# gest-mod.net
KiCad netlist of a schematic drawn in EAGLE
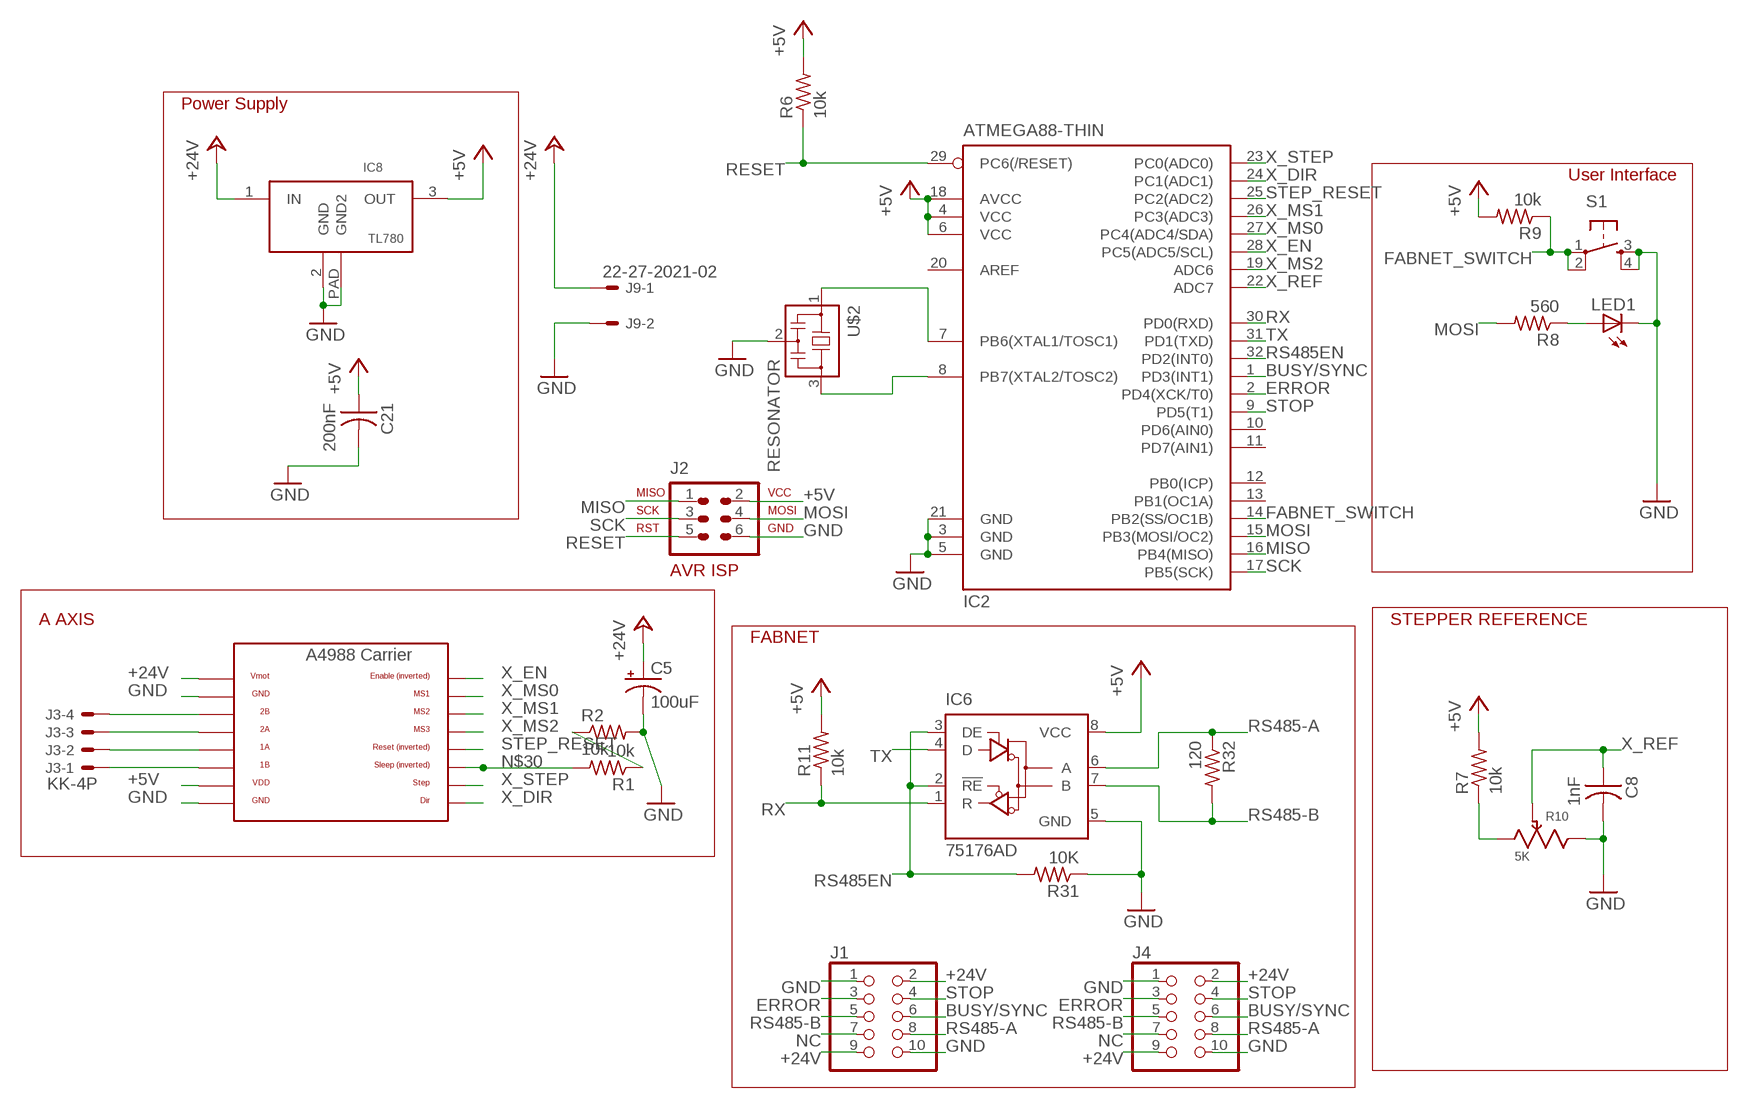
[diagram p0: schematic, sheet 1]

(export (version "E")
  (design (tool "Eeschema 10.0.6"))
  (components
    (comp (ref "C5")
      (value "100uF")
      (footprint "eagle-import:PANASONIC_D")
      (libsource (lib "eagle-import") (part "CPOL-USD"))
    )
    (comp (ref "C8")
      (value "1nF")
      (footprint "eagle-import:C1206FAB")
      (libsource (lib "eagle-import") (part "CAP-US1206FAB"))
    )
    (comp (ref "C21")
      (value "200nF")
      (footprint "eagle-import:C1206FAB")
      (libsource (lib "eagle-import") (part "CAP-US1206FAB"))
    )
    (comp (ref "IC2")
      (value "ATMEGA88-THIN")
      (footprint "eagle-import:TQFP32-08THIN")
      (libsource (lib "eagle-import") (part "ATMEGA88-THIN"))
    )
    (comp (ref "IC6")
      (value "75176AD")
      (footprint "eagle-import:D_R-PDSO-G8")
      (libsource (lib "eagle-import") (part "75176AD"))
    )
    (comp (ref "IC8")
      (value "TL780_VREG")
      (footprint "eagle-import:D2PAK-3")
      (libsource (lib "eagle-import") (part "TL780_VREG"))
    )
    (comp (ref "J1")
      (value "PINHEAD_PINHD-2X5")
      (footprint "eagle-import:PINHEAD_2X05")
      (libsource (lib "eagle-import") (part "PINHEAD_PINHD-2X5"))
    )
    (comp (ref "J2")
      (value "AVR-7_AVR-ISP-6VERT")
      (footprint "eagle-import:AVR-7_AVR-ISP-6")
      (libsource (lib "eagle-import") (part "AVR-7_AVR-ISP-6VERT"))
    )
    (comp (ref "J3")
      (value "KK-4P")
      (footprint "eagle-import:7395-04")
      (libsource (lib "eagle-import") (part "22-?-0405-7048"))
    )
    (comp (ref "J4")
      (value "PINHEAD_PINHD-2X5")
      (footprint "eagle-import:PINHEAD_2X05")
      (libsource (lib "eagle-import") (part "PINHEAD_PINHD-2X5"))
    )
    (comp (ref "J9")
      (value "22-27-2021-02")
      (footprint "eagle-import:6410-02")
      (libsource (lib "eagle-import") (part "22-?-0227-2021"))
    )
    (comp (ref "LED1")
      (value "LEDCHIPLED_1206")
      (footprint "eagle-import:CHIPLED_1206")
      (libsource (lib "eagle-import") (part "LEDCHIPLED_1206"))
    )
    (comp (ref "R1")
      (value "10k")
      (footprint "eagle-import:R1206FAB")
      (libsource (lib "eagle-import") (part "RES-US1206FAB"))
    )
    (comp (ref "R2")
      (value "10k")
      (footprint "eagle-import:R1206FAB")
      (libsource (lib "eagle-import") (part "RES-US1206FAB"))
    )
    (comp (ref "R6")
      (value "10k")
      (footprint "eagle-import:R1206FAB")
      (libsource (lib "eagle-import") (part "RES-US1206FAB"))
    )
    (comp (ref "R7")
      (value "10k")
      (footprint "eagle-import:R1206FAB")
      (libsource (lib "eagle-import") (part "RES-US1206FAB"))
    )
    (comp (ref "R8")
      (value "560")
      (footprint "eagle-import:R1206FAB")
      (libsource (lib "eagle-import") (part "RES-US1206FAB"))
    )
    (comp (ref "R9")
      (value "10k")
      (footprint "eagle-import:R1206FAB")
      (libsource (lib "eagle-import") (part "RES-US1206FAB"))
    )
    (comp (ref "R10")
      (value "5K")
      (footprint "eagle-import:BOURN_TRIM")
      (libsource (lib "eagle-import") (part "BOURN_POT"))
    )
    (comp (ref "R11")
      (value "10k")
      (footprint "eagle-import:R1206FAB")
      (libsource (lib "eagle-import") (part "RES-US1206FAB"))
    )
    (comp (ref "R31")
      (value "10K")
      (footprint "eagle-import:R1206FAB")
      (libsource (lib "eagle-import") (part "RES-US1206FAB"))
    )
    (comp (ref "R32")
      (value "120")
      (footprint "eagle-import:R1206FAB")
      (libsource (lib "eagle-import") (part "RES-US1206FAB"))
    )
    (comp (ref "S1")
      (value "6MM_SWITCH6MM_SWITCH")
      (footprint "eagle-import:6MM_SWITCH")
      (libsource (lib "eagle-import") (part "6MM_SWITCH6MM_SWITCH"))
    )
    (comp (ref "U$2")
      (value "RESONATOR")
      (footprint "eagle-import:EFOBM")
      (libsource (lib "eagle-import") (part "RESONATOR"))
    )
    (comp (ref "U$5")
      (value "REPRAPJR_A4988BREAKOUT")
      (footprint "eagle-import:REPRAPJR_A4988BREAKOUT")
      (libsource (lib "eagle-import") (part "REPRAPJR_A4988BREAKOUT"))
    )
  )
  (nets
    (net (code "1") (name "+5V") (class "Default")
      (node (ref "C21") (pin "1") (pinfunction "1_1") (pintype "passive"))
      (node (ref "IC2") (pin "18") (pinfunction "AVCC_18") (pintype "power_in"))
      (node (ref "IC2") (pin "4") (pinfunction "VCC_4") (pintype "power_in"))
      (node (ref "IC2") (pin "6") (pinfunction "VCC_6") (pintype "power_in"))
      (node (ref "IC6") (pin "8") (pinfunction "VCC_8") (pintype "power_in"))
      (node (ref "IC8") (pin "3") (pinfunction "OUT_3") (pintype "bidirectional"))
      (node (ref "J2") (pin "2") (pinfunction "2_2") (pintype "passive"))
      (node (ref "R11") (pin "2") (pinfunction "2_2") (pintype "passive"))
      (node (ref "R6") (pin "2") (pinfunction "2_2") (pintype "passive"))
      (node (ref "R7") (pin "2") (pinfunction "2_2") (pintype "passive"))
      (node (ref "R9") (pin "2") (pinfunction "2_2") (pintype "passive"))
      (node (ref "U$5") (pin "VDD") (pinfunction "VDD_VDD") (pintype "power_in"))
    )
    (net (code "2") (name "+24V") (class "Default")
      (node (ref "C5") (pin "+") (pinfunction "+_+") (pintype "passive"))
      (node (ref "IC8") (pin "1") (pinfunction "IN_1") (pintype "bidirectional"))
      (node (ref "J1") (pin "2") (pinfunction "2_2") (pintype "passive"))
      (node (ref "J1") (pin "9") (pinfunction "9_9") (pintype "passive"))
      (node (ref "J4") (pin "2") (pinfunction "2_2") (pintype "passive"))
      (node (ref "J4") (pin "9") (pinfunction "9_9") (pintype "passive"))
      (node (ref "J9") (pin "1") (pinfunction "S_1") (pintype "passive"))
      (node (ref "U$5") (pin "VMOT") (pinfunction "VMOT_VMOT") (pintype "power_in"))
    )
    (net (code "3") (name "/BUSY{slash}SYNC") (class "Default")
      (node (ref "IC2") (pin "1") (pinfunction "PD3(INT1)_1") (pintype "bidirectional"))
      (node (ref "J1") (pin "6") (pinfunction "6_6") (pintype "passive"))
      (node (ref "J4") (pin "6") (pinfunction "6_6") (pintype "passive"))
    )
    (net (code "4") (name "/ERROR") (class "Default")
      (node (ref "IC2") (pin "2") (pinfunction "PD4(XCK/T0)_2") (pintype "bidirectional"))
      (node (ref "J1") (pin "3") (pinfunction "3_3") (pintype "passive"))
      (node (ref "J4") (pin "3") (pinfunction "3_3") (pintype "passive"))
    )
    (net (code "5") (name "/FABNET_SWITCH") (class "Default")
      (node (ref "IC2") (pin "14") (pinfunction "PB2(SS/OC1B)_14") (pintype "bidirectional"))
      (node (ref "R9") (pin "1") (pinfunction "1_1") (pintype "passive"))
      (node (ref "S1") (pin "1") (pinfunction "P_1") (pintype "passive"))
      (node (ref "S1") (pin "2") (pinfunction "P1_2") (pintype "passive"))
    )
    (net (code "6") (name "/MISO") (class "Default")
      (node (ref "IC2") (pin "16") (pinfunction "PB4(MISO)_16") (pintype "bidirectional"))
      (node (ref "J2") (pin "1") (pinfunction "1_1") (pintype "passive"))
    )
    (net (code "7") (name "/MOSI") (class "Default")
      (node (ref "IC2") (pin "15") (pinfunction "PB3(MOSI/OC2)_15") (pintype "bidirectional"))
      (node (ref "J2") (pin "4") (pinfunction "4_4") (pintype "passive"))
      (node (ref "R8") (pin "2") (pinfunction "2_2") (pintype "passive"))
    )
    (net (code "8") (name "/N$30") (class "Default")
      (node (ref "R1") (pin "2") (pinfunction "2_2") (pintype "passive"))
      (node (ref "U$5") (pin "SLP") (pinfunction "SLEEP_SLP") (pintype "input"))
    )
    (net (code "9") (name "/NC") (class "Default")
      (node (ref "J1") (pin "7") (pinfunction "7_7") (pintype "passive"))
      (node (ref "J4") (pin "7") (pinfunction "7_7") (pintype "passive"))
    )
    (net (code "10") (name "/RESET") (class "Default")
      (node (ref "IC2") (pin "29") (pinfunction "PC6(/RESET)_29") (pintype "bidirectional"))
      (node (ref "J2") (pin "5") (pinfunction "5_5") (pintype "passive"))
      (node (ref "R6") (pin "1") (pinfunction "1_1") (pintype "passive"))
    )
    (net (code "11") (name "/RS485-A") (class "Default")
      (node (ref "IC6") (pin "6") (pinfunction "A_6") (pintype "output"))
      (node (ref "J1") (pin "8") (pinfunction "8_8") (pintype "passive"))
      (node (ref "J4") (pin "8") (pinfunction "8_8") (pintype "passive"))
      (node (ref "R32") (pin "1") (pinfunction "1_1") (pintype "passive"))
    )
    (net (code "12") (name "/RS485-B") (class "Default")
      (node (ref "IC6") (pin "7") (pinfunction "B_7") (pintype "output"))
      (node (ref "J1") (pin "5") (pinfunction "5_5") (pintype "passive"))
      (node (ref "J4") (pin "5") (pinfunction "5_5") (pintype "passive"))
      (node (ref "R32") (pin "2") (pinfunction "2_2") (pintype "passive"))
    )
    (net (code "13") (name "/RS485EN") (class "Default")
      (node (ref "IC2") (pin "32") (pinfunction "PD2(INT0)_32") (pintype "bidirectional"))
      (node (ref "IC6") (pin "2") (pinfunction "~{RE}_2") (pintype "input"))
      (node (ref "IC6") (pin "3") (pinfunction "DE_3") (pintype "input"))
      (node (ref "R31") (pin "2") (pinfunction "2_2") (pintype "passive"))
    )
    (net (code "14") (name "/RX") (class "Default")
      (node (ref "IC2") (pin "30") (pinfunction "PD0(RXD)_30") (pintype "bidirectional"))
      (node (ref "IC6") (pin "1") (pinfunction "R_1") (pintype "input"))
      (node (ref "R11") (pin "1") (pinfunction "1_1") (pintype "passive"))
    )
    (net (code "15") (name "/SCK") (class "Default")
      (node (ref "IC2") (pin "17") (pinfunction "PB5(SCK)_17") (pintype "bidirectional"))
      (node (ref "J2") (pin "3") (pinfunction "3_3") (pintype "passive"))
    )
    (net (code "16") (name "/STEP_RESET") (class "Default")
      (node (ref "IC2") (pin "25") (pinfunction "PC2(ADC2)_25") (pintype "bidirectional"))
      (node (ref "U$5") (pin "RST") (pinfunction "RST_RST") (pintype "input"))
    )
    (net (code "17") (name "/STOP") (class "Default")
      (node (ref "IC2") (pin "9") (pinfunction "PD5(T1)_9") (pintype "bidirectional"))
      (node (ref "J1") (pin "4") (pinfunction "4_4") (pintype "passive"))
      (node (ref "J4") (pin "4") (pinfunction "4_4") (pintype "passive"))
    )
    (net (code "18") (name "/TX") (class "Default")
      (node (ref "IC2") (pin "31") (pinfunction "PD1(TXD)_31") (pintype "bidirectional"))
      (node (ref "IC6") (pin "4") (pinfunction "D_4") (pintype "input"))
    )
    (net (code "19") (name "/X_DIR") (class "Default")
      (node (ref "IC2") (pin "24") (pinfunction "PC1(ADC1)_24") (pintype "bidirectional"))
      (node (ref "U$5") (pin "DIR") (pinfunction "DIR_DIR") (pintype "input"))
    )
    (net (code "20") (name "/X_EN") (class "Default")
      (node (ref "IC2") (pin "28") (pinfunction "PC5(ADC5/SCL)_28") (pintype "bidirectional"))
      (node (ref "U$5") (pin "EN") (pinfunction "EN_EN") (pintype "input"))
    )
    (net (code "21") (name "/X_MS0") (class "Default")
      (node (ref "IC2") (pin "27") (pinfunction "PC4(ADC4/SDA)_27") (pintype "bidirectional"))
      (node (ref "U$5") (pin "MS1") (pinfunction "MS1_MS1") (pintype "input"))
    )
    (net (code "22") (name "/X_MS1") (class "Default")
      (node (ref "IC2") (pin "26") (pinfunction "PC3(ADC3)_26") (pintype "bidirectional"))
      (node (ref "U$5") (pin "MS2") (pinfunction "MS2_MS2") (pintype "input"))
    )
    (net (code "23") (name "/X_MS2") (class "Default")
      (node (ref "IC2") (pin "19") (pinfunction "ADC6_19") (pintype "bidirectional"))
      (node (ref "U$5") (pin "MS3") (pinfunction "MS3_MS3") (pintype "input"))
    )
    (net (code "24") (name "/X_REF") (class "Default")
      (node (ref "C8") (pin "1") (pinfunction "1_1") (pintype "passive"))
      (node (ref "IC2") (pin "22") (pinfunction "ADC7_22") (pintype "bidirectional"))
      (node (ref "R10") (pin "2") (pinfunction "2_2") (pintype "bidirectional"))
    )
    (net (code "25") (name "/X_STEP") (class "Default")
      (node (ref "IC2") (pin "23") (pinfunction "PC0(ADC0)_23") (pintype "bidirectional"))
      (node (ref "U$5") (pin "STEP") (pinfunction "STEP_STEP") (pintype "input"))
    )
    (net (code "26") (name "GND") (class "Default")
      (node (ref "C21") (pin "2") (pinfunction "2_2") (pintype "passive"))
      (node (ref "C5") (pin "-") (pinfunction "-_-") (pintype "passive"))
      (node (ref "C8") (pin "2") (pinfunction "2_2") (pintype "passive"))
      (node (ref "IC2") (pin "21") (pinfunction "GND_21") (pintype "power_in"))
      (node (ref "IC2") (pin "3") (pinfunction "GND_3") (pintype "power_in"))
      (node (ref "IC2") (pin "5") (pinfunction "GND_5") (pintype "power_in"))
      (node (ref "IC6") (pin "5") (pinfunction "GND_5") (pintype "power_in"))
      (node (ref "IC8") (pin "2") (pinfunction "GND_2") (pintype "bidirectional"))
      (node (ref "IC8") (pin "PAD") (pinfunction "GND2_PAD") (pintype "bidirectional"))
      (node (ref "J1") (pin "1") (pinfunction "1_1") (pintype "passive"))
      (node (ref "J1") (pin "10") (pinfunction "10_10") (pintype "passive"))
      (node (ref "J2") (pin "6") (pinfunction "6_6") (pintype "passive"))
      (node (ref "J4") (pin "1") (pinfunction "1_1") (pintype "passive"))
      (node (ref "J4") (pin "10") (pinfunction "10_10") (pintype "passive"))
      (node (ref "J9") (pin "2") (pinfunction "S_2") (pintype "passive"))
      (node (ref "LED1") (pin "C") (pinfunction "C_C") (pintype "passive"))
      (node (ref "R10") (pin "3") (pinfunction "3_3") (pintype "bidirectional"))
      (node (ref "R2") (pin "2") (pinfunction "2_2") (pintype "passive"))
      (node (ref "R31") (pin "1") (pinfunction "1_1") (pintype "passive"))
      (node (ref "S1") (pin "3") (pinfunction "S_3") (pintype "passive"))
      (node (ref "S1") (pin "4") (pinfunction "S1_4") (pintype "passive"))
      (node (ref "U$2") (pin "2") (pinfunction "2_2") (pintype "passive"))
      (node (ref "U$5") (pin "GND") (pinfunction "GND_GND") (pintype "power_in"))
      (node (ref "U$5") (pin "GND@0") (pinfunction "GND_GND@0") (pintype "power_in"))
    )
    (net (code "27") (name "Net-(IC2-PB6(XTAL1{slash}TOSC1))") (class "Default")
      (node (ref "IC2") (pin "7") (pinfunction "PB6(XTAL1/TOSC1)_7") (pintype "bidirectional"))
      (node (ref "U$2") (pin "1") (pinfunction "1_1") (pintype "passive"))
    )
    (net (code "28") (name "Net-(IC2-PB7(XTAL2{slash}TOSC2))") (class "Default")
      (node (ref "IC2") (pin "8") (pinfunction "PB7(XTAL2/TOSC2)_8") (pintype "bidirectional"))
      (node (ref "U$2") (pin "3") (pinfunction "3_3") (pintype "passive"))
    )
    (net (code "29") (name "Net-(J3A-S)") (class "Default")
      (node (ref "J3") (pin "1") (pinfunction "S_1") (pintype "passive"))
      (node (ref "U$5") (pin "1B") (pinfunction "1B_1B") (pintype "output"))
    )
    (net (code "30") (name "Net-(J3B-S)") (class "Default")
      (node (ref "J3") (pin "2") (pinfunction "S_2") (pintype "passive"))
      (node (ref "U$5") (pin "1A") (pinfunction "1A_1A") (pintype "output"))
    )
    (net (code "31") (name "Net-(J3C-S)") (class "Default")
      (node (ref "J3") (pin "3") (pinfunction "S_3") (pintype "passive"))
      (node (ref "U$5") (pin "2A") (pinfunction "2A_2A") (pintype "output"))
    )
    (net (code "32") (name "Net-(J3D-S)") (class "Default")
      (node (ref "J3") (pin "4") (pinfunction "S_4") (pintype "passive"))
      (node (ref "U$5") (pin "2B") (pinfunction "2B_2B") (pintype "output"))
    )
    (net (code "33") (name "Net-(LED1-PadA)") (class "Default")
      (node (ref "LED1") (pin "A") (pinfunction "A_A") (pintype "passive"))
      (node (ref "R8") (pin "1") (pinfunction "1_1") (pintype "passive"))
    )
    (net (code "34") (name "Net-(R1-Pad1)") (class "Default")
      (node (ref "R1") (pin "1") (pinfunction "1_1") (pintype "passive"))
      (node (ref "R2") (pin "1") (pinfunction "1_1") (pintype "passive"))
    )
    (net (code "35") (name "Net-(R10-Pad1)") (class "Default")
      (node (ref "R10") (pin "1") (pinfunction "1_1") (pintype "bidirectional"))
      (node (ref "R7") (pin "1") (pinfunction "1_1") (pintype "passive"))
    )
    (net (code "36") (name "unconnected-(IC2-AREF-Pad20)") (class "Default")
      (node (ref "IC2") (pin "20") (pinfunction "AREF_20") (pintype "passive"))
    )
    (net (code "37") (name "unconnected-(IC2-PB0(ICP)-Pad12)") (class "Default")
      (node (ref "IC2") (pin "12") (pinfunction "PB0(ICP)_12") (pintype "bidirectional"))
    )
    (net (code "38") (name "unconnected-(IC2-PB1(OC1A)-Pad13)") (class "Default")
      (node (ref "IC2") (pin "13") (pinfunction "PB1(OC1A)_13") (pintype "bidirectional"))
    )
    (net (code "39") (name "unconnected-(IC2-PD6(AIN0)-Pad10)") (class "Default")
      (node (ref "IC2") (pin "10") (pinfunction "PD6(AIN0)_10") (pintype "bidirectional"))
    )
    (net (code "40") (name "unconnected-(IC2-PD7(AIN1)-Pad11)") (class "Default")
      (node (ref "IC2") (pin "11") (pinfunction "PD7(AIN1)_11") (pintype "bidirectional"))
    )
  )
)
